# mainPower.net
KiCad netlist of a schematic drawn in Altium Designer
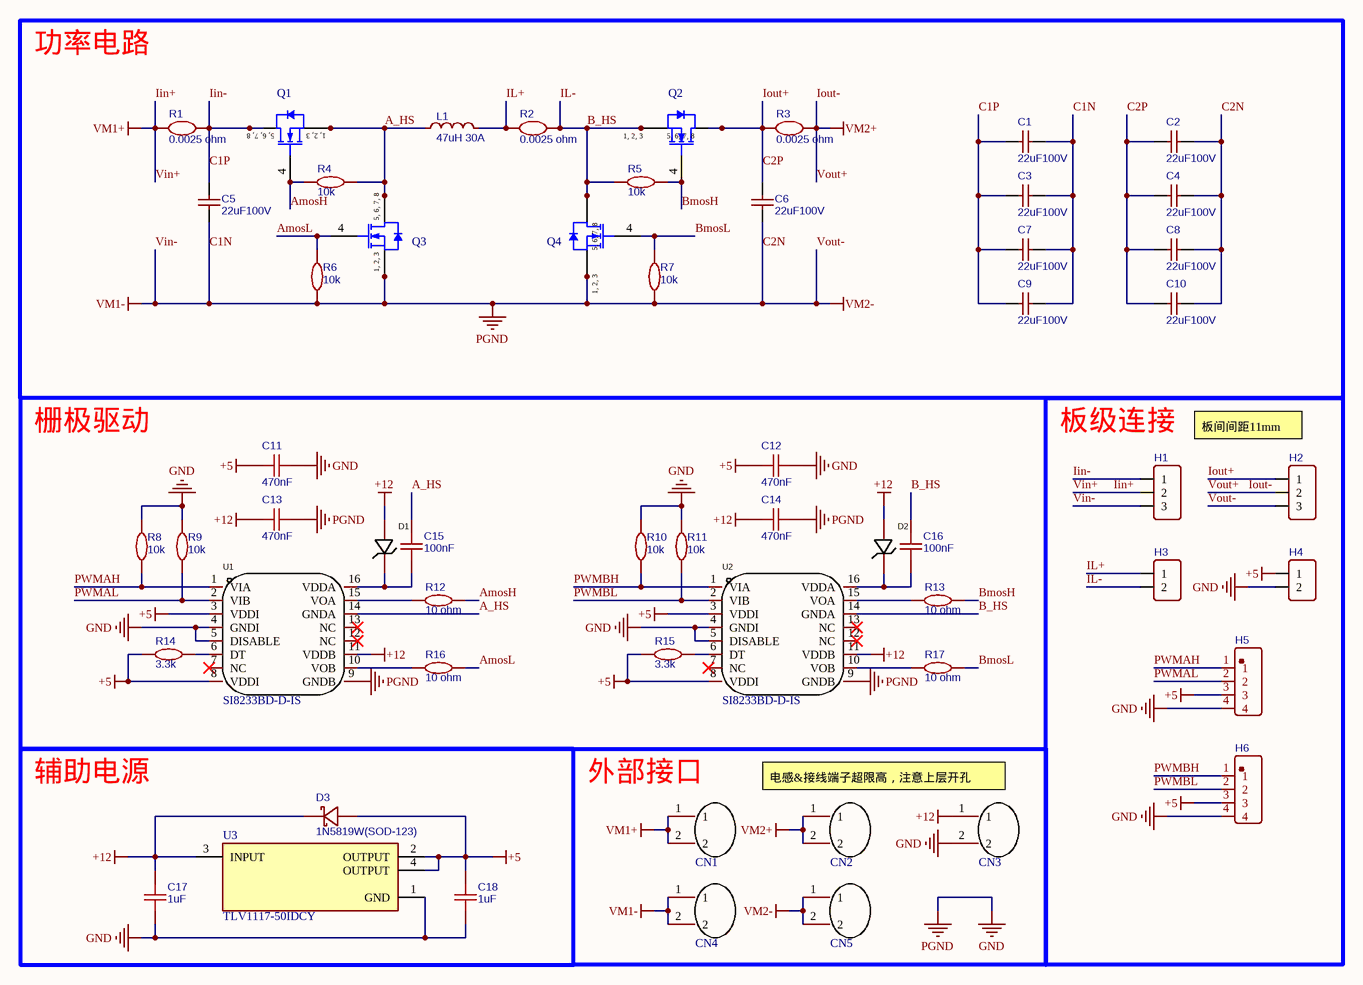
[diagram p0: mainPower.SchDoc]

(export (version "E")
  (design (tool "Eeschema 10.0.6"))
  (components
    (comp (ref "C1")
      (value "22uF100V")
      (footprint "C1206")
      (fields
        (field (name "BOM_MANUFACTURER PART") "1206B102K202NT")
        (field (name "BOM_SUPPLIER PART") "C9196")
      )
      (libsource (lib "RC_schlib") (part "C1206"))
    )
    (comp (ref "C2")
      (value "22uF100V")
      (footprint "C1206")
      (fields
        (field (name "BOM_MANUFACTURER PART") "1206B102K202NT")
        (field (name "BOM_SUPPLIER PART") "C9196")
      )
      (libsource (lib "RC_schlib") (part "C1206"))
    )
    (comp (ref "C3")
      (value "22uF100V")
      (footprint "C1206")
      (fields
        (field (name "BOM_MANUFACTURER PART") "1206B102K202NT")
        (field (name "BOM_SUPPLIER PART") "C9196")
      )
      (libsource (lib "RC_schlib") (part "C1206"))
    )
    (comp (ref "C4")
      (value "22uF100V")
      (footprint "C1206")
      (fields
        (field (name "BOM_MANUFACTURER PART") "1206B102K202NT")
        (field (name "BOM_SUPPLIER PART") "C9196")
      )
      (libsource (lib "RC_schlib") (part "C1206"))
    )
    (comp (ref "C5")
      (value "22uF100V")
      (footprint "C1206")
      (fields
        (field (name "BOM_MANUFACTURER PART") "1206B102K202NT")
        (field (name "BOM_SUPPLIER PART") "C9196")
      )
      (libsource (lib "RC_schlib") (part "C1206"))
    )
    (comp (ref "C6")
      (value "22uF100V")
      (footprint "C1206")
      (fields
        (field (name "BOM_MANUFACTURER PART") "1206B102K202NT")
        (field (name "BOM_SUPPLIER PART") "C9196")
      )
      (libsource (lib "RC_schlib") (part "C1206"))
    )
    (comp (ref "C7")
      (value "22uF100V")
      (footprint "C1206")
      (fields
        (field (name "BOM_MANUFACTURER PART") "1206B102K202NT")
        (field (name "BOM_SUPPLIER PART") "C9196")
      )
      (libsource (lib "RC_schlib") (part "C1206"))
    )
    (comp (ref "C8")
      (value "22uF100V")
      (footprint "C1206")
      (fields
        (field (name "BOM_MANUFACTURER PART") "1206B102K202NT")
        (field (name "BOM_SUPPLIER PART") "C9196")
      )
      (libsource (lib "RC_schlib") (part "C1206"))
    )
    (comp (ref "C9")
      (value "22uF100V")
      (footprint "C1206")
      (fields
        (field (name "BOM_MANUFACTURER PART") "1206B102K202NT")
        (field (name "BOM_SUPPLIER PART") "C9196")
      )
      (libsource (lib "RC_schlib") (part "C1206"))
    )
    (comp (ref "C10")
      (value "22uF100V")
      (footprint "C1206")
      (fields
        (field (name "BOM_MANUFACTURER PART") "1206B102K202NT")
        (field (name "BOM_SUPPLIER PART") "C9196")
      )
      (libsource (lib "RC_schlib") (part "C1206"))
    )
    (comp (ref "C11")
      (value "470nF")
      (footprint "C0603")
      (fields
        (field (name "BOM_MANUFACTURER PART") "CC0603KRX7R9BB104")
        (field (name "BOM_SUPPLIER PART") "C14663")
      )
      (libsource (lib "RC_schlib") (part "C0603"))
    )
    (comp (ref "C12")
      (value "470nF")
      (footprint "C0603")
      (fields
        (field (name "BOM_MANUFACTURER PART") "CC0603KRX7R9BB104")
        (field (name "BOM_SUPPLIER PART") "C14663")
      )
      (libsource (lib "RC_schlib") (part "C0603"))
    )
    (comp (ref "C13")
      (value "470nF")
      (footprint "C0603")
      (fields
        (field (name "BOM_MANUFACTURER PART") "CC0603KRX7R9BB104")
        (field (name "BOM_SUPPLIER PART") "C14663")
      )
      (libsource (lib "RC_schlib") (part "C0603"))
    )
    (comp (ref "C14")
      (value "470nF")
      (footprint "C0603")
      (fields
        (field (name "BOM_MANUFACTURER PART") "CC0603KRX7R9BB104")
        (field (name "BOM_SUPPLIER PART") "C14663")
      )
      (libsource (lib "RC_schlib") (part "C0603"))
    )
    (comp (ref "C15")
      (value "100nF")
      (footprint "C0603")
      (fields
        (field (name "BOM_MANUFACTURER PART") "CC0603KRX7R9BB104")
        (field (name "BOM_SUPPLIER PART") "C14663")
      )
      (libsource (lib "RC_schlib") (part "C0603"))
    )
    (comp (ref "C16")
      (value "100nF")
      (footprint "C0603")
      (fields
        (field (name "BOM_MANUFACTURER PART") "CC0603KRX7R9BB104")
        (field (name "BOM_SUPPLIER PART") "C14663")
      )
      (libsource (lib "RC_schlib") (part "C0603"))
    )
    (comp (ref "C17")
      (value "1uF")
      (footprint "C0603")
      (fields
        (field (name "BOM_MANUFACTURER PART") "CC0603KRX7R9BB104")
        (field (name "BOM_SUPPLIER PART") "C14663")
      )
      (libsource (lib "RC_schlib") (part "C0603"))
    )
    (comp (ref "C18")
      (value "1uF")
      (footprint "C0603")
      (fields
        (field (name "BOM_MANUFACTURER PART") "CC0603KRX7R9BB104")
        (field (name "BOM_SUPPLIER PART") "C14663")
      )
      (libsource (lib "RC_schlib") (part "C0603"))
    )
    (comp (ref "CN1")
      (value "1729128")
      (footprint "CONN-TH_2P-P5.08")
      (description "间距:5.08mm;排数:1;每排PIN数:2;安装方式:直针;额定电流:13.5A;额定电压:400V;工作温度范围:-;颜色:绿色;")
      (fields (field (name "MANUFACTURER") "Phoenix Contact(菲尼克斯)"))
      (libsource (lib "MKDSN") (part "MKDSN5.08-2P"))
    )
    (comp (ref "CN2")
      (value "1729128")
      (footprint "CONN-TH_2P-P5.08")
      (description "间距:5.08mm;排数:1;每排PIN数:2;安装方式:直针;额定电流:13.5A;额定电压:400V;工作温度范围:-;颜色:绿色;")
      (fields (field (name "MANUFACTURER") "Phoenix Contact(菲尼克斯)"))
      (libsource (lib "MKDSN") (part "MKDSN5.08-2P"))
    )
    (comp (ref "CN3")
      (value "1729128")
      (footprint "CONN-TH_2P-P5.08")
      (description "间距:5.08mm;排数:1;每排PIN数:2;安装方式:直针;额定电流:13.5A;额定电压:400V;工作温度范围:-;颜色:绿色;")
      (fields (field (name "MANUFACTURER") "Phoenix Contact(菲尼克斯)"))
      (libsource (lib "MKDSN") (part "MKDSN5.08-2P"))
    )
    (comp (ref "CN4")
      (value "1729128")
      (footprint "CONN-TH_2P-P5.08")
      (description "间距:5.08mm;排数:1;每排PIN数:2;安装方式:直针;额定电流:13.5A;额定电压:400V;工作温度范围:-;颜色:绿色;")
      (fields (field (name "MANUFACTURER") "Phoenix Contact(菲尼克斯)"))
      (libsource (lib "MKDSN") (part "MKDSN5.08-2P"))
    )
    (comp (ref "CN5")
      (value "1729128")
      (footprint "CONN-TH_2P-P5.08")
      (description "间距:5.08mm;排数:1;每排PIN数:2;安装方式:直针;额定电流:13.5A;额定电压:400V;工作温度范围:-;颜色:绿色;")
      (fields (field (name "MANUFACTURER") "Phoenix Contact(菲尼克斯)"))
      (libsource (lib "MKDSN") (part "MKDSN5.08-2P"))
    )
    (comp (ref "D1")
      (value "MURA120T3G")
      (footprint "SMA")
      (description "25ns 0.875V压降 1A快恢复二极管")
      (fields (field (name "MANUFACTURER") "MDD") (field (name "MANUFACTURER PART") "ES1J"))
      (libsource (lib "Diode_schlib") (part "MURA120T3G"))
    )
    (comp (ref "D2")
      (value "MURA120T3G")
      (footprint "SMA")
      (description "25ns 0.875V压降 1A快恢复二极管")
      (fields (field (name "MANUFACTURER") "MDD") (field (name "MANUFACTURER PART") "ES1J"))
      (libsource (lib "Diode_schlib") (part "MURA120T3G"))
    )
    (comp (ref "D3")
      (value "1N5819W(SOD-123)")
      (footprint "SOD-123")
      (fields
        (field (name "BOM_SUPPLIER PART") "C2931787")
        (field (name "BOM_MANUFACTURER PART") "SS34")
        (field (name "CONTRIBUTOR") "LCSC")
      )
      (libsource (lib "Diode_schlib") (part "1N5819W(SOD-123)"))
    )
    (comp (ref "H1")
      (value "Header-Male-2.54_1x3")
      (footprint "HDR2.54-LI-3P")
      (fields
        (field (name "BOM_MANUFACTURER PART") "Header2.54mm 1*3P")
        (field (name "BOM_SUPPLIER PART") "C49257")
      )
      (libsource (lib "2.54CN_schlib") (part "Header-Male-2.54_1x3"))
    )
    (comp (ref "H2")
      (value "Header-Male-2.54_1x3")
      (footprint "HDR2.54-LI-3P")
      (fields
        (field (name "BOM_MANUFACTURER PART") "Header2.54mm 1*3P")
        (field (name "BOM_SUPPLIER PART") "C49257")
      )
      (libsource (lib "2.54CN_schlib") (part "Header-Male-2.54_1x3"))
    )
    (comp (ref "H3")
      (value "Header-Male-2.54_1x2")
      (footprint "HDR2.54-LI-2P")
      (fields
        (field (name "BOM_MANUFACTURER PART") "Header2.54mm 1*3P")
        (field (name "BOM_SUPPLIER PART") "C49257")
      )
      (libsource (lib "2.54CN_schlib") (part "Header-Male-2.54_1x2"))
    )
    (comp (ref "H4")
      (value "Header-Male-2.54_1x2")
      (footprint "HDR2.54-LI-2P")
      (fields
        (field (name "BOM_MANUFACTURER PART") "Header2.54mm 1*3P")
        (field (name "BOM_SUPPLIER PART") "C49257")
      )
      (libsource (lib "2.54CN_schlib") (part "Header-Male-2.54_1x2"))
    )
    (comp (ref "H5")
      (value "Header-Male-2.54_1x4")
      (footprint "HDR2.54-LI-4P")
      (fields (field (name "BOM_SUPPLIER PART") "C247921") (field (name "CONTRIBUTOR") "LCSC"))
      (libsource (lib "2.54CN_schlib") (part "Header-Male-2.54_1x4"))
    )
    (comp (ref "H6")
      (value "Header-Male-2.54_1x4")
      (footprint "HDR2.54-LI-4P")
      (fields (field (name "BOM_SUPPLIER PART") "C247921") (field (name "CONTRIBUTOR") "LCSC"))
      (libsource (lib "2.54CN_schlib") (part "Header-Male-2.54_1x4"))
    )
    (comp (ref "L1")
      (value "47uH 30A")
      (footprint "106-125立式")
      (fields
        (field (name "BOM_SUPPLIER PART") "C2936653")
        (field (name "BOM_MANUFACTURER PART") "HA42-4R7MT")
        (field (name "CONTRIBUTOR") "LCSC")
      )
      (libsource (lib "Inductance_schlib") (part "106-125铁硅铝磁环电感"))
    )
    (comp (ref "Q1")
      (value "BSC070N10NS3 G")
      (footprint "INF-PG-TDSON-8-1_V")
      (fields
        (field (name "MANUFACTURER") "Infineon")
        (field (name "MANUFACTURER PART NUMBER") "BSC070N10NS3G")
      )
      (libsource (lib "MOSFET_schlib") (part "BSC070N10NS3G"))
    )
    (comp (ref "Q2")
      (value "BSC070N10NS3 G")
      (footprint "INF-PG-TDSON-8-1_V")
      (fields
        (field (name "MANUFACTURER") "Infineon")
        (field (name "MANUFACTURER PART NUMBER") "BSC070N10NS3G")
      )
      (libsource (lib "MOSFET_schlib") (part "BSC070N10NS3G"))
    )
    (comp (ref "Q3")
      (value "BSC070N10NS3 G")
      (footprint "INF-PG-TDSON-8-1_V")
      (fields
        (field (name "MANUFACTURER") "Infineon")
        (field (name "MANUFACTURER PART NUMBER") "BSC070N10NS3G")
      )
      (libsource (lib "MOSFET_schlib") (part "BSC070N10NS3G"))
    )
    (comp (ref "Q4")
      (value "BSC070N10NS3 G")
      (footprint "INF-PG-TDSON-8-1_V")
      (fields
        (field (name "MANUFACTURER") "Infineon")
        (field (name "MANUFACTURER PART NUMBER") "BSC070N10NS3G")
      )
      (libsource (lib "MOSFET_schlib") (part "BSC070N10NS3G"))
    )
    (comp (ref "R1")
      (value "0.0025 ohm")
      (footprint "R2512")
      (fields
        (field (name "BOM_SUPPLIER PART") "C375694")
        (field (name "BOM_MANUFACTURER PART") "SR2512FK-0751RL")
        (field (name "CONTRIBUTOR") "LCSC")
      )
      (libsource (lib "RC_schlib") (part "R2512"))
    )
    (comp (ref "R2")
      (value "0.0025 ohm")
      (footprint "R2512")
      (fields
        (field (name "BOM_SUPPLIER PART") "C375694")
        (field (name "BOM_MANUFACTURER PART") "SR2512FK-0751RL")
        (field (name "CONTRIBUTOR") "LCSC")
      )
      (libsource (lib "RC_schlib") (part "R2512"))
    )
    (comp (ref "R3")
      (value "0.0025 ohm")
      (footprint "R2512")
      (fields
        (field (name "BOM_SUPPLIER PART") "C375694")
        (field (name "BOM_MANUFACTURER PART") "SR2512FK-0751RL")
        (field (name "CONTRIBUTOR") "LCSC")
      )
      (libsource (lib "RC_schlib") (part "R2512"))
    )
    (comp (ref "R4")
      (value "10k")
      (footprint "R0603")
      (fields
        (field (name "BOM_SUPPLIER PART") "C326890")
        (field (name "BOM_MANUFACTURER PART") "SR0603JR-071RL")
        (field (name "CONTRIBUTOR") "LCSC")
      )
      (libsource (lib "RC_schlib") (part "R0603"))
    )
    (comp (ref "R5")
      (value "10k")
      (footprint "R0603")
      (fields
        (field (name "BOM_SUPPLIER PART") "C326890")
        (field (name "BOM_MANUFACTURER PART") "SR0603JR-071RL")
        (field (name "CONTRIBUTOR") "LCSC")
      )
      (libsource (lib "RC_schlib") (part "R0603"))
    )
    (comp (ref "R6")
      (value "10k")
      (footprint "R0603")
      (fields
        (field (name "BOM_SUPPLIER PART") "C326890")
        (field (name "BOM_MANUFACTURER PART") "SR0603JR-071RL")
        (field (name "CONTRIBUTOR") "LCSC")
      )
      (libsource (lib "RC_schlib") (part "R0603"))
    )
    (comp (ref "R7")
      (value "10k")
      (footprint "R0603")
      (fields
        (field (name "BOM_SUPPLIER PART") "C326890")
        (field (name "BOM_MANUFACTURER PART") "SR0603JR-071RL")
        (field (name "CONTRIBUTOR") "LCSC")
      )
      (libsource (lib "RC_schlib") (part "R0603"))
    )
    (comp (ref "R8")
      (value "10k")
      (footprint "R0603")
      (fields
        (field (name "BOM_SUPPLIER PART") "C326890")
        (field (name "BOM_MANUFACTURER PART") "SR0603JR-071RL")
        (field (name "CONTRIBUTOR") "LCSC")
      )
      (libsource (lib "RC_schlib") (part "R0603"))
    )
    (comp (ref "R9")
      (value "10k")
      (footprint "R0603")
      (fields
        (field (name "BOM_SUPPLIER PART") "C326890")
        (field (name "BOM_MANUFACTURER PART") "SR0603JR-071RL")
        (field (name "CONTRIBUTOR") "LCSC")
      )
      (libsource (lib "RC_schlib") (part "R0603"))
    )
    (comp (ref "R10")
      (value "10k")
      (footprint "R0603")
      (fields
        (field (name "BOM_SUPPLIER PART") "C326890")
        (field (name "BOM_MANUFACTURER PART") "SR0603JR-071RL")
        (field (name "CONTRIBUTOR") "LCSC")
      )
      (libsource (lib "RC_schlib") (part "R0603"))
    )
    (comp (ref "R11")
      (value "10k")
      (footprint "R0603")
      (fields
        (field (name "BOM_SUPPLIER PART") "C326890")
        (field (name "BOM_MANUFACTURER PART") "SR0603JR-071RL")
        (field (name "CONTRIBUTOR") "LCSC")
      )
      (libsource (lib "RC_schlib") (part "R0603"))
    )
    (comp (ref "R12")
      (value "10 ohm")
      (footprint "R0603")
      (fields
        (field (name "BOM_SUPPLIER PART") "C326890")
        (field (name "BOM_MANUFACTURER PART") "SR0603JR-071RL")
        (field (name "CONTRIBUTOR") "LCSC")
      )
      (libsource (lib "RC_schlib") (part "R0603"))
    )
    (comp (ref "R13")
      (value "10 ohm")
      (footprint "R0603")
      (fields
        (field (name "BOM_SUPPLIER PART") "C326890")
        (field (name "BOM_MANUFACTURER PART") "SR0603JR-071RL")
        (field (name "CONTRIBUTOR") "LCSC")
      )
      (libsource (lib "RC_schlib") (part "R0603"))
    )
    (comp (ref "R14")
      (value "3.3k")
      (footprint "R0603")
      (fields
        (field (name "BOM_SUPPLIER PART") "C326890")
        (field (name "BOM_MANUFACTURER PART") "SR0603JR-071RL")
        (field (name "CONTRIBUTOR") "LCSC")
      )
      (libsource (lib "RC_schlib") (part "R0603"))
    )
    (comp (ref "R15")
      (value "3.3k")
      (footprint "R0603")
      (fields
        (field (name "BOM_SUPPLIER PART") "C326890")
        (field (name "BOM_MANUFACTURER PART") "SR0603JR-071RL")
        (field (name "CONTRIBUTOR") "LCSC")
      )
      (libsource (lib "RC_schlib") (part "R0603"))
    )
    (comp (ref "R16")
      (value "10 ohm")
      (footprint "R0603")
      (fields
        (field (name "BOM_SUPPLIER PART") "C326890")
        (field (name "BOM_MANUFACTURER PART") "SR0603JR-071RL")
        (field (name "CONTRIBUTOR") "LCSC")
      )
      (libsource (lib "RC_schlib") (part "R0603"))
    )
    (comp (ref "R17")
      (value "10 ohm")
      (footprint "R0603")
      (fields
        (field (name "BOM_SUPPLIER PART") "C326890")
        (field (name "BOM_MANUFACTURER PART") "SR0603JR-071RL")
        (field (name "CONTRIBUTOR") "LCSC")
      )
      (libsource (lib "RC_schlib") (part "R0603"))
    )
    (comp (ref "U1")
      (value "SI8233BD-D-IS")
      (footprint "SOIC-16_L10.3-W7.5-P1.27-LS10.3-BL")
      (description "高速隔离半桥栅极驱动器")
      (fields (field (name "MANUFACTURER") "SILICON LABS(芯科)"))
      (libsource (lib "IC_schlib") (part "SI8233BD-D-IS"))
    )
    (comp (ref "U2")
      (value "SI8233BD-D-IS")
      (footprint "SOIC-16_L10.3-W7.5-P1.27-LS10.3-BL")
      (description "高速隔离半桥栅极驱动器")
      (fields (field (name "MANUFACTURER") "SILICON LABS(芯科)"))
      (libsource (lib "IC_schlib") (part "SI8233BD-D-IS"))
    )
    (comp (ref "U3")
      (value "TLV1117-50IDCY")
      (footprint "FP-DCY0004A-MFG")
      (description "IC REG LINEAR 5V 800MA SOT223-4")
      (libsource (lib "Altium Content Vault") (part "e308c0431133a401381f8e374ae96fd"))
    )
  )
  (nets
    (net (code "1") (name "+5") (class "Default")
      (node (ref "C11") (pin "2") (pinfunction "2_2") (pintype "passive"))
      (node (ref "C12") (pin "2") (pinfunction "2_2") (pintype "passive"))
      (node (ref "C18") (pin "2") (pinfunction "2_2") (pintype "passive"))
      (node (ref "D3") (pin "1") (pinfunction "A_1") (pintype "passive"))
      (node (ref "H4") (pin "1") (pinfunction "1_1") (pintype "passive"))
      (node (ref "H5") (pin "3") (pinfunction "3_3") (pintype "passive"))
      (node (ref "H6") (pin "3") (pinfunction "3_3") (pintype "passive"))
      (node (ref "R14") (pin "1") (pinfunction "1_1") (pintype "passive"))
      (node (ref "R15") (pin "1") (pinfunction "1_1") (pintype "passive"))
      (node (ref "U1") (pin "3") (pinfunction "VDDI_3") (pintype "passive"))
      (node (ref "U1") (pin "8") (pinfunction "VDDI_8") (pintype "passive"))
      (node (ref "U2") (pin "3") (pinfunction "VDDI_3") (pintype "passive"))
      (node (ref "U2") (pin "8") (pinfunction "VDDI_8") (pintype "passive"))
      (node (ref "U3") (pin "2") (pinfunction "OUTPUT_2") (pintype "power_in"))
      (node (ref "U3") (pin "4") (pinfunction "OUTPUT_4") (pintype "power_in"))
    )
    (net (code "2") (name "+12") (class "Default")
      (node (ref "C13") (pin "2") (pinfunction "2_2") (pintype "passive"))
      (node (ref "C14") (pin "2") (pinfunction "2_2") (pintype "passive"))
      (node (ref "C17") (pin "2") (pinfunction "2_2") (pintype "passive"))
      (node (ref "CN3") (pin "1") (pinfunction "1_1") (pintype "passive"))
      (node (ref "D1") (pin "1") (pinfunction "A_1") (pintype "passive"))
      (node (ref "D2") (pin "1") (pinfunction "A_1") (pintype "passive"))
      (node (ref "D3") (pin "2") (pinfunction "K_2") (pintype "passive"))
      (node (ref "U1") (pin "11") (pinfunction "VDDB_11") (pintype "passive"))
      (node (ref "U2") (pin "11") (pinfunction "VDDB_11") (pintype "passive"))
      (node (ref "U3") (pin "3") (pinfunction "INPUT_3") (pintype "power_in"))
    )
    (net (code "3") (name "/A_HS") (class "Default")
      (node (ref "C15") (pin "2") (pinfunction "2_2") (pintype "passive"))
      (node (ref "L1") (pin "1") (pinfunction "1_1") (pintype "passive"))
      (node (ref "Q1") (pin "1") (pinfunction "SOURCE_1") (pintype "passive"))
      (node (ref "Q1") (pin "2") (pinfunction "SOURCE_2") (pintype "passive"))
      (node (ref "Q1") (pin "3") (pinfunction "SOURCE_3") (pintype "passive"))
      (node (ref "Q3") (pin "5") (pinfunction "DRAIN_5") (pintype "passive"))
      (node (ref "Q3") (pin "6") (pinfunction "DRAIN_6") (pintype "passive"))
      (node (ref "Q3") (pin "7") (pinfunction "DRAIN_7") (pintype "passive"))
      (node (ref "Q3") (pin "8") (pinfunction "DRAIN_8") (pintype "passive"))
      (node (ref "R4") (pin "1") (pinfunction "1_1") (pintype "passive"))
      (node (ref "U1") (pin "14") (pinfunction "GNDA_14") (pintype "passive"))
    )
    (net (code "4") (name "/AmosH") (class "Default")
      (node (ref "Q1") (pin "4") (pinfunction "GATE_4") (pintype "passive"))
      (node (ref "R12") (pin "2") (pinfunction "2_2") (pintype "passive"))
      (node (ref "R4") (pin "2") (pinfunction "2_2") (pintype "passive"))
    )
    (net (code "5") (name "/AmosL") (class "Default")
      (node (ref "Q3") (pin "4") (pinfunction "GATE_4") (pintype "passive"))
      (node (ref "R16") (pin "2") (pinfunction "2_2") (pintype "passive"))
      (node (ref "R6") (pin "2") (pinfunction "2_2") (pintype "passive"))
    )
    (net (code "6") (name "/B_HS") (class "Default")
      (node (ref "C16") (pin "2") (pinfunction "2_2") (pintype "passive"))
      (node (ref "H3") (pin "2") (pinfunction "2_2") (pintype "passive"))
      (node (ref "Q2") (pin "1") (pinfunction "SOURCE_1") (pintype "passive"))
      (node (ref "Q2") (pin "2") (pinfunction "SOURCE_2") (pintype "passive"))
      (node (ref "Q2") (pin "3") (pinfunction "SOURCE_3") (pintype "passive"))
      (node (ref "Q4") (pin "5") (pinfunction "DRAIN_5") (pintype "passive"))
      (node (ref "Q4") (pin "6") (pinfunction "DRAIN_6") (pintype "passive"))
      (node (ref "Q4") (pin "7") (pinfunction "DRAIN_7") (pintype "passive"))
      (node (ref "Q4") (pin "8") (pinfunction "DRAIN_8") (pintype "passive"))
      (node (ref "R2") (pin "2") (pinfunction "2_2") (pintype "passive"))
      (node (ref "R5") (pin "2") (pinfunction "2_2") (pintype "passive"))
      (node (ref "U2") (pin "14") (pinfunction "GNDA_14") (pintype "passive"))
    )
    (net (code "7") (name "/BmosH") (class "Default")
      (node (ref "Q2") (pin "4") (pinfunction "GATE_4") (pintype "passive"))
      (node (ref "R13") (pin "2") (pinfunction "2_2") (pintype "passive"))
      (node (ref "R5") (pin "1") (pinfunction "1_1") (pintype "passive"))
    )
    (net (code "8") (name "/BmosL") (class "Default")
      (node (ref "Q4") (pin "4") (pinfunction "GATE_4") (pintype "passive"))
      (node (ref "R17") (pin "2") (pinfunction "2_2") (pintype "passive"))
      (node (ref "R7") (pin "2") (pinfunction "2_2") (pintype "passive"))
    )
    (net (code "9") (name "/C1P") (class "Default")
      (node (ref "C1") (pin "1") (pinfunction "1_1") (pintype "passive"))
      (node (ref "C3") (pin "1") (pinfunction "1_1") (pintype "passive"))
      (node (ref "C5") (pin "2") (pinfunction "2_2") (pintype "passive"))
      (node (ref "C7") (pin "1") (pinfunction "1_1") (pintype "passive"))
      (node (ref "C9") (pin "1") (pinfunction "1_1") (pintype "passive"))
      (node (ref "H1") (pin "1") (pinfunction "1_1") (pintype "passive"))
      (node (ref "Q1") (pin "5") (pinfunction "DRAIN_5") (pintype "passive"))
      (node (ref "Q1") (pin "6") (pinfunction "DRAIN_6") (pintype "passive"))
      (node (ref "Q1") (pin "7") (pinfunction "DRAIN_7") (pintype "passive"))
      (node (ref "Q1") (pin "8") (pinfunction "DRAIN_8") (pintype "passive"))
      (node (ref "R1") (pin "2") (pinfunction "2_2") (pintype "passive"))
    )
    (net (code "10") (name "/C2P") (class "Default")
      (node (ref "C10") (pin "1") (pinfunction "1_1") (pintype "passive"))
      (node (ref "C2") (pin "1") (pinfunction "1_1") (pintype "passive"))
      (node (ref "C4") (pin "1") (pinfunction "1_1") (pintype "passive"))
      (node (ref "C6") (pin "2") (pinfunction "2_2") (pintype "passive"))
      (node (ref "C8") (pin "1") (pinfunction "1_1") (pintype "passive"))
      (node (ref "H2") (pin "1") (pinfunction "1_1") (pintype "passive"))
      (node (ref "Q2") (pin "5") (pinfunction "DRAIN_5") (pintype "passive"))
      (node (ref "Q2") (pin "6") (pinfunction "DRAIN_6") (pintype "passive"))
      (node (ref "Q2") (pin "7") (pinfunction "DRAIN_7") (pintype "passive"))
      (node (ref "Q2") (pin "8") (pinfunction "DRAIN_8") (pintype "passive"))
      (node (ref "R3") (pin "1") (pinfunction "1_1") (pintype "passive"))
    )
    (net (code "11") (name "/IL+") (class "Default")
      (node (ref "H3") (pin "1") (pinfunction "1_1") (pintype "passive"))
      (node (ref "L1") (pin "2") (pinfunction "2_2") (pintype "passive"))
      (node (ref "R2") (pin "1") (pinfunction "1_1") (pintype "passive"))
    )
    (net (code "12") (name "/PWMAH") (class "Default")
      (node (ref "H5") (pin "1") (pinfunction "1_1") (pintype "passive"))
      (node (ref "R8") (pin "1") (pinfunction "1_1") (pintype "passive"))
      (node (ref "U1") (pin "1") (pinfunction "VIA_1") (pintype "passive"))
    )
    (net (code "13") (name "/PWMAL") (class "Default")
      (node (ref "H5") (pin "2") (pinfunction "2_2") (pintype "passive"))
      (node (ref "R9") (pin "1") (pinfunction "1_1") (pintype "passive"))
      (node (ref "U1") (pin "2") (pinfunction "VIB_2") (pintype "passive"))
    )
    (net (code "14") (name "/PWMBH") (class "Default")
      (node (ref "H6") (pin "1") (pinfunction "1_1") (pintype "passive"))
      (node (ref "R10") (pin "1") (pinfunction "1_1") (pintype "passive"))
      (node (ref "U2") (pin "1") (pinfunction "VIA_1") (pintype "passive"))
    )
    (net (code "15") (name "/PWMBL") (class "Default")
      (node (ref "H6") (pin "2") (pinfunction "2_2") (pintype "passive"))
      (node (ref "R11") (pin "1") (pinfunction "1_1") (pintype "passive"))
      (node (ref "U2") (pin "2") (pinfunction "VIB_2") (pintype "passive"))
    )
    (net (code "16") (name "GND") (class "Default")
      (node (ref "C1") (pin "2") (pinfunction "2_2") (pintype "passive"))
      (node (ref "C10") (pin "2") (pinfunction "2_2") (pintype "passive"))
      (node (ref "C11") (pin "1") (pinfunction "1_1") (pintype "passive"))
      (node (ref "C12") (pin "1") (pinfunction "1_1") (pintype "passive"))
      (node (ref "C13") (pin "1") (pinfunction "1_1") (pintype "passive"))
      (node (ref "C14") (pin "1") (pinfunction "1_1") (pintype "passive"))
      (node (ref "C17") (pin "1") (pinfunction "1_1") (pintype "passive"))
      (node (ref "C18") (pin "1") (pinfunction "1_1") (pintype "passive"))
      (node (ref "C2") (pin "2") (pinfunction "2_2") (pintype "passive"))
      (node (ref "C3") (pin "2") (pinfunction "2_2") (pintype "passive"))
      (node (ref "C4") (pin "2") (pinfunction "2_2") (pintype "passive"))
      (node (ref "C5") (pin "1") (pinfunction "1_1") (pintype "passive"))
      (node (ref "C6") (pin "1") (pinfunction "1_1") (pintype "passive"))
      (node (ref "C7") (pin "2") (pinfunction "2_2") (pintype "passive"))
      (node (ref "C8") (pin "2") (pinfunction "2_2") (pintype "passive"))
      (node (ref "C9") (pin "2") (pinfunction "2_2") (pintype "passive"))
      (node (ref "CN3") (pin "2") (pinfunction "2_2") (pintype "passive"))
      (node (ref "CN4") (pin "1") (pinfunction "1_1") (pintype "passive"))
      (node (ref "CN4") (pin "2") (pinfunction "2_2") (pintype "passive"))
      (node (ref "CN5") (pin "1") (pinfunction "1_1") (pintype "passive"))
      (node (ref "CN5") (pin "2") (pinfunction "2_2") (pintype "passive"))
      (node (ref "H1") (pin "3") (pinfunction "3_3") (pintype "passive"))
      (node (ref "H2") (pin "3") (pinfunction "3_3") (pintype "passive"))
      (node (ref "H4") (pin "2") (pinfunction "2_2") (pintype "passive"))
      (node (ref "H5") (pin "4") (pinfunction "4_4") (pintype "passive"))
      (node (ref "H6") (pin "4") (pinfunction "4_4") (pintype "passive"))
      (node (ref "Q3") (pin "1") (pinfunction "SOURCE_1") (pintype "passive"))
      (node (ref "Q3") (pin "2") (pinfunction "SOURCE_2") (pintype "passive"))
      (node (ref "Q3") (pin "3") (pinfunction "SOURCE_3") (pintype "passive"))
      (node (ref "Q4") (pin "1") (pinfunction "SOURCE_1") (pintype "passive"))
      (node (ref "Q4") (pin "2") (pinfunction "SOURCE_2") (pintype "passive"))
      (node (ref "Q4") (pin "3") (pinfunction "SOURCE_3") (pintype "passive"))
      (node (ref "R10") (pin "2") (pinfunction "2_2") (pintype "passive"))
      (node (ref "R11") (pin "2") (pinfunction "2_2") (pintype "passive"))
      (node (ref "R6") (pin "1") (pinfunction "1_1") (pintype "passive"))
      (node (ref "R7") (pin "1") (pinfunction "1_1") (pintype "passive"))
      (node (ref "R8") (pin "2") (pinfunction "2_2") (pintype "passive"))
      (node (ref "R9") (pin "2") (pinfunction "2_2") (pintype "passive"))
      (node (ref "U1") (pin "4") (pinfunction "GNDI_4") (pintype "passive"))
      (node (ref "U1") (pin "5") (pinfunction "DISABLE_5") (pintype "passive"))
      (node (ref "U1") (pin "9") (pinfunction "GNDB_9") (pintype "passive"))
      (node (ref "U2") (pin "4") (pinfunction "GNDI_4") (pintype "passive"))
      (node (ref "U2") (pin "5") (pinfunction "DISABLE_5") (pintype "passive"))
      (node (ref "U2") (pin "9") (pinfunction "GNDB_9") (pintype "passive"))
      (node (ref "U3") (pin "1") (pinfunction "GND_1") (pintype "power_in"))
    )
    (net (code "17") (name "Net-(D1-C)") (class "Default")
      (node (ref "C15") (pin "1") (pinfunction "1_1") (pintype "passive"))
      (node (ref "D1") (pin "2") (pinfunction "C_2") (pintype "passive"))
      (node (ref "U1") (pin "16") (pinfunction "VDDA_16") (pintype "passive"))
    )
    (net (code "18") (name "Net-(D2-C)") (class "Default")
      (node (ref "C16") (pin "1") (pinfunction "1_1") (pintype "passive"))
      (node (ref "D2") (pin "2") (pinfunction "C_2") (pintype "passive"))
      (node (ref "U2") (pin "16") (pinfunction "VDDA_16") (pintype "passive"))
    )
    (net (code "19") (name "Net-(U1-DT)") (class "Default")
      (node (ref "R14") (pin "2") (pinfunction "2_2") (pintype "passive"))
      (node (ref "U1") (pin "6") (pinfunction "DT_6") (pintype "passive"))
    )
    (net (code "20") (name "Net-(U1-VOA)") (class "Default")
      (node (ref "R12") (pin "1") (pinfunction "1_1") (pintype "passive"))
      (node (ref "U1") (pin "15") (pinfunction "VOA_15") (pintype "passive"))
    )
    (net (code "21") (name "Net-(U1-VOB)") (class "Default")
      (node (ref "R16") (pin "1") (pinfunction "1_1") (pintype "passive"))
      (node (ref "U1") (pin "10") (pinfunction "VOB_10") (pintype "passive"))
    )
    (net (code "22") (name "Net-(U2-DT)") (class "Default")
      (node (ref "R15") (pin "2") (pinfunction "2_2") (pintype "passive"))
      (node (ref "U2") (pin "6") (pinfunction "DT_6") (pintype "passive"))
    )
    (net (code "23") (name "Net-(U2-VOA)") (class "Default")
      (node (ref "R13") (pin "1") (pinfunction "1_1") (pintype "passive"))
      (node (ref "U2") (pin "15") (pinfunction "VOA_15") (pintype "passive"))
    )
    (net (code "24") (name "Net-(U2-VOB)") (class "Default")
      (node (ref "R17") (pin "1") (pinfunction "1_1") (pintype "passive"))
      (node (ref "U2") (pin "10") (pinfunction "VOB_10") (pintype "passive"))
    )
    (net (code "25") (name "VM1+") (class "Default")
      (node (ref "CN1") (pin "1") (pinfunction "1_1") (pintype "passive"))
      (node (ref "CN1") (pin "2") (pinfunction "2_2") (pintype "passive"))
      (node (ref "H1") (pin "2") (pinfunction "2_2") (pintype "passive"))
      (node (ref "R1") (pin "1") (pinfunction "1_1") (pintype "passive"))
    )
    (net (code "26") (name "VM2+") (class "Default")
      (node (ref "CN2") (pin "1") (pinfunction "1_1") (pintype "passive"))
      (node (ref "CN2") (pin "2") (pinfunction "2_2") (pintype "passive"))
      (node (ref "H2") (pin "2") (pinfunction "2_2") (pintype "passive"))
      (node (ref "R3") (pin "2") (pinfunction "2_2") (pintype "passive"))
    )
    (net (code "27") (name "unconnected-(U1-NC-Pad7)") (class "Default")
      (node (ref "U1") (pin "7") (pinfunction "NC_7") (pintype "passive+no_connect"))
    )
    (net (code "28") (name "unconnected-(U1-NC-Pad12)") (class "Default")
      (node (ref "U1") (pin "12") (pinfunction "NC_12") (pintype "passive+no_connect"))
    )
    (net (code "29") (name "unconnected-(U1-NC-Pad13)") (class "Default")
      (node (ref "U1") (pin "13") (pinfunction "NC_13") (pintype "passive+no_connect"))
    )
    (net (code "30") (name "unconnected-(U2-NC-Pad7)") (class "Default")
      (node (ref "U2") (pin "7") (pinfunction "NC_7") (pintype "passive+no_connect"))
    )
    (net (code "31") (name "unconnected-(U2-NC-Pad12)") (class "Default")
      (node (ref "U2") (pin "12") (pinfunction "NC_12") (pintype "passive+no_connect"))
    )
    (net (code "32") (name "unconnected-(U2-NC-Pad13)") (class "Default")
      (node (ref "U2") (pin "13") (pinfunction "NC_13") (pintype "passive+no_connect"))
    )
  )
)
